# Nutriente_superior.net
KiCad netlist of a schematic drawn in EAGLE
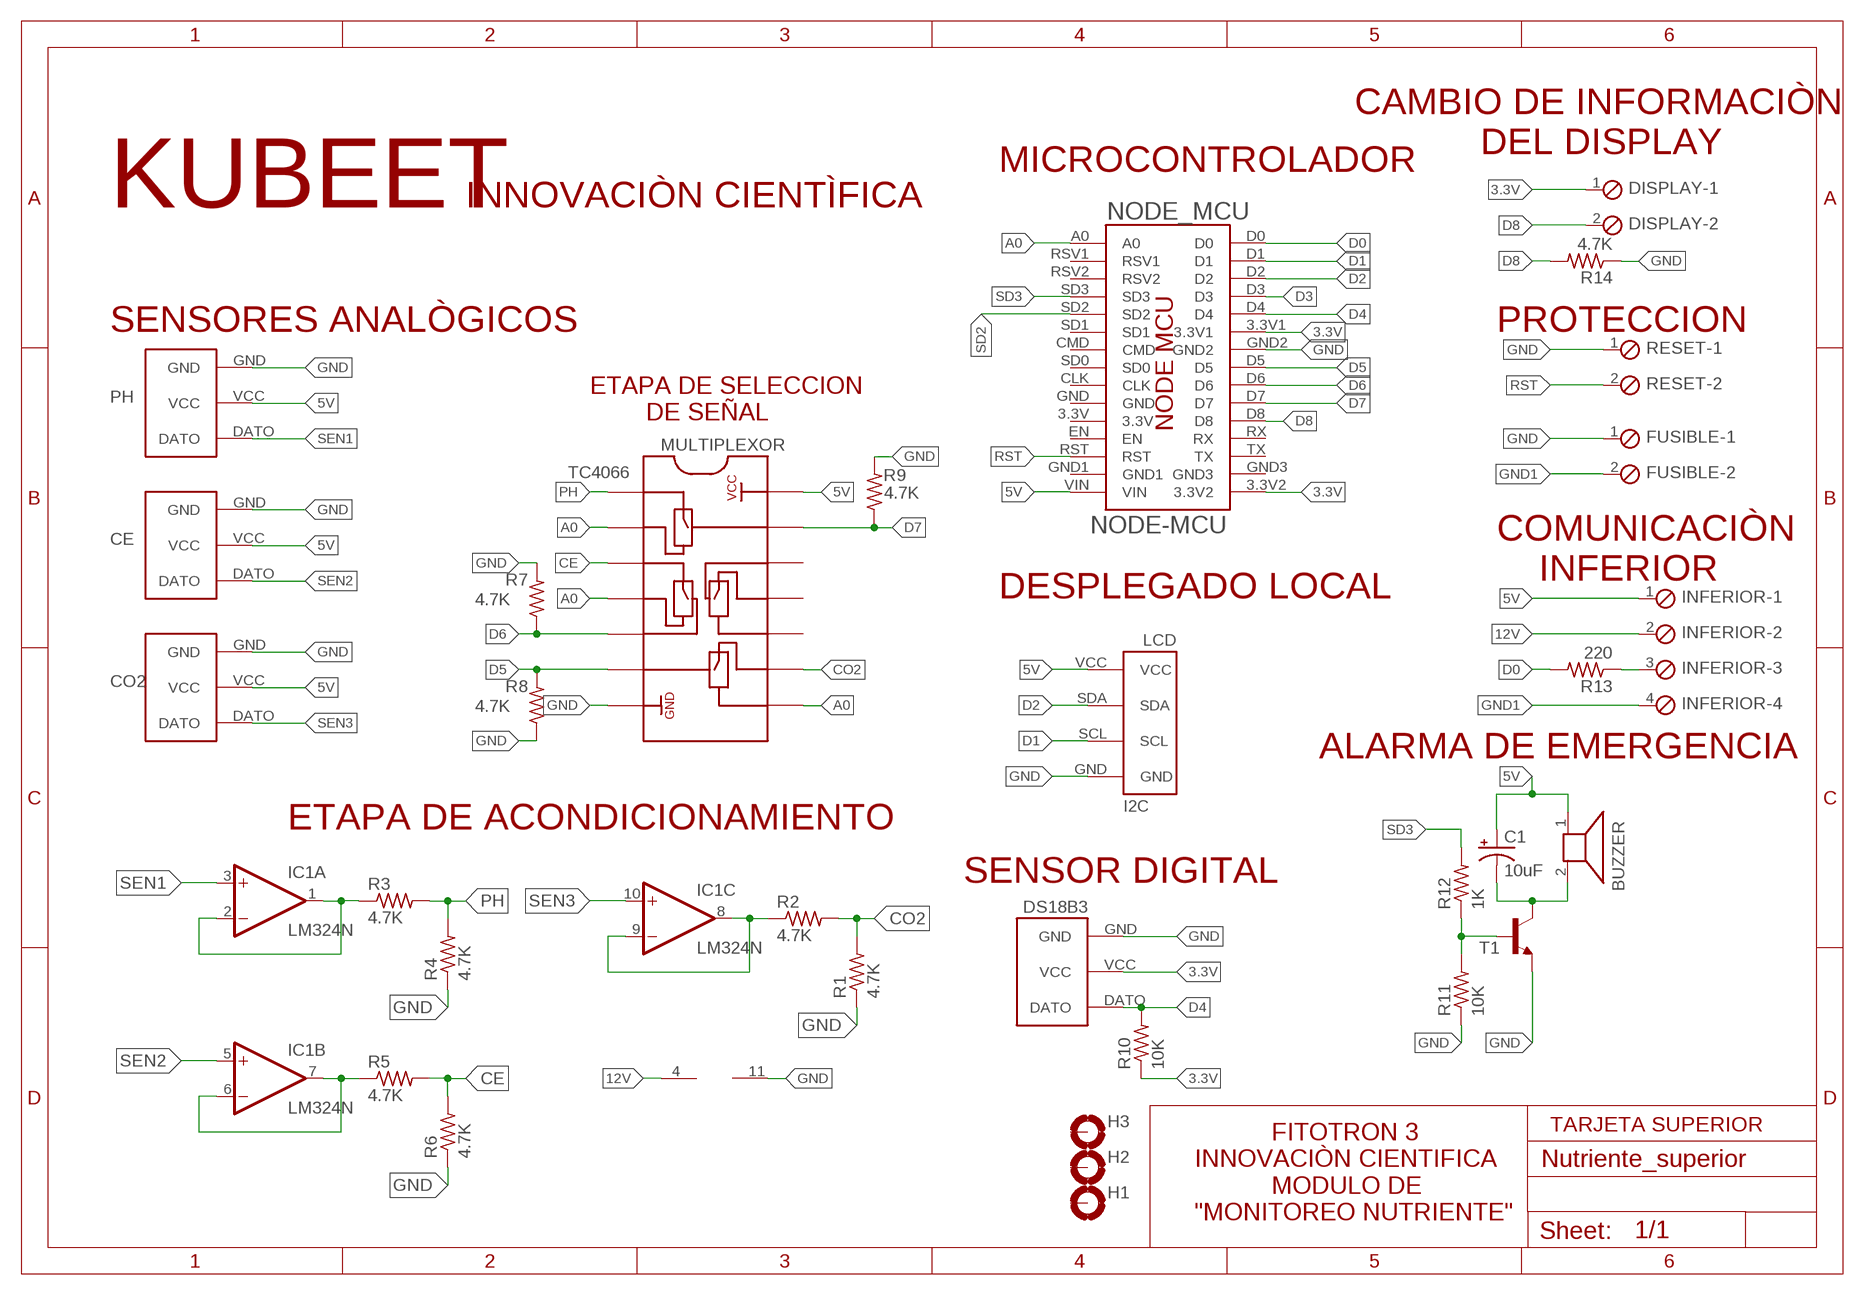
[diagram p0: schematic, sheet 1]

(export (version "E")
  (design (tool "Eeschema 10.0.6"))
  (components
    (comp (ref "BUZZER")
      (value "AL60P")
      (footprint "eagle-import:AL60P")
      (libsource (lib "eagle-import") (part "AL60P"))
    )
    (comp (ref "C1")
      (value "10uF")
      (footprint "eagle-import:E2,5-6")
      (libsource (lib "eagle-import") (part "CPOL-USE2.5-6"))
    )
    (comp (ref "CE")
      (value "BASE")
      (footprint "eagle-import:BASE")
      (libsource (lib "eagle-import") (part "BASE"))
    )
    (comp (ref "CO2")
      (value "BASE")
      (footprint "eagle-import:BASE")
      (libsource (lib "eagle-import") (part "BASE"))
    )
    (comp (ref "DISPLAY")
      (value "MPT2")
      (footprint "eagle-import:2POL254")
      (libsource (lib "eagle-import") (part "MPT2"))
    )
    (comp (ref "DS18B3")
      (value "BASE")
      (footprint "eagle-import:BASE")
      (libsource (lib "eagle-import") (part "BASE"))
    )
    (comp (ref "FUSIBLE")
      (value "MPT2")
      (footprint "eagle-import:2POL254")
      (libsource (lib "eagle-import") (part "MPT2"))
    )
    (comp (ref "H1")
      (value "MOUNT-PAD-ROUND3.0")
      (footprint "eagle-import:3,0-PAD")
      (libsource (lib "eagle-import") (part "MOUNT-PAD-ROUND3.0"))
    )
    (comp (ref "H2")
      (value "MOUNT-PAD-ROUND3.0")
      (footprint "eagle-import:3,0-PAD")
      (libsource (lib "eagle-import") (part "MOUNT-PAD-ROUND3.0"))
    )
    (comp (ref "H3")
      (value "MOUNT-PAD-ROUND3.0")
      (footprint "eagle-import:3,0-PAD")
      (libsource (lib "eagle-import") (part "MOUNT-PAD-ROUND3.0"))
    )
    (comp (ref "IC1")
      (value "LM324N")
      (footprint "eagle-import:DIL14")
      (libsource (lib "eagle-import") (part "LM324N"))
    )
    (comp (ref "INFERIOR")
      (value "MPT4")
      (footprint "eagle-import:4POL254")
      (libsource (lib "eagle-import") (part "MPT4"))
    )
    (comp (ref "LCD")
      (value "I2C")
      (footprint "eagle-import:I2C")
      (libsource (lib "eagle-import") (part "I2C"))
    )
    (comp (ref "MULTIPLEXOR")
      (value "TC4066")
      (footprint "eagle-import:TC4066")
      (libsource (lib "eagle-import") (part "TC4066"))
    )
    (comp (ref "NODE_MCU")
      (value "NODE-MCU")
      (footprint "eagle-import:NODE-MCU")
      (libsource (lib "eagle-import") (part "NODE-MCU"))
    )
    (comp (ref "PH")
      (value "BASE")
      (footprint "eagle-import:BASE")
      (libsource (lib "eagle-import") (part "BASE"))
    )
    (comp (ref "R1")
      (value "4.7K")
      (footprint "eagle-import:0207_7")
      (libsource (lib "eagle-import") (part "R-US_0207/7"))
    )
    (comp (ref "R2")
      (value "4.7K")
      (footprint "eagle-import:0207_7")
      (libsource (lib "eagle-import") (part "R-US_0207/7"))
    )
    (comp (ref "R3")
      (value "4.7K")
      (footprint "eagle-import:0207_7")
      (libsource (lib "eagle-import") (part "R-US_0207/7"))
    )
    (comp (ref "R4")
      (value "4.7K")
      (footprint "eagle-import:0207_7")
      (libsource (lib "eagle-import") (part "R-US_0207/7"))
    )
    (comp (ref "R5")
      (value "4.7K")
      (footprint "eagle-import:0207_7")
      (libsource (lib "eagle-import") (part "R-US_0207/7"))
    )
    (comp (ref "R6")
      (value "4.7K")
      (footprint "eagle-import:0207_7")
      (libsource (lib "eagle-import") (part "R-US_0207/7"))
    )
    (comp (ref "R7")
      (value "4.7K")
      (footprint "eagle-import:0207_7")
      (libsource (lib "eagle-import") (part "R-US_0207/7"))
    )
    (comp (ref "R8")
      (value "4.7K")
      (footprint "eagle-import:0207_7")
      (libsource (lib "eagle-import") (part "R-US_0207/7"))
    )
    (comp (ref "R9")
      (value "4.7K")
      (footprint "eagle-import:0207_7")
      (libsource (lib "eagle-import") (part "R-US_0207/7"))
    )
    (comp (ref "R10")
      (value "10K")
      (footprint "eagle-import:0207_7")
      (libsource (lib "eagle-import") (part "R-US_0207/7"))
    )
    (comp (ref "R11")
      (value "10K")
      (footprint "eagle-import:0207_7")
      (libsource (lib "eagle-import") (part "R-US_0207/7"))
    )
    (comp (ref "R12")
      (value "1K")
      (footprint "eagle-import:0207_7")
      (libsource (lib "eagle-import") (part "R-US_0207/7"))
    )
    (comp (ref "R13")
      (value "220")
      (footprint "eagle-import:0207_10")
      (libsource (lib "eagle-import") (part "R-US_0207/10"))
    )
    (comp (ref "R14")
      (value "4.7K")
      (footprint "eagle-import:0207_7")
      (libsource (lib "eagle-import") (part "R-US_0207/7"))
    )
    (comp (ref "RESET")
      (value "MPT2")
      (footprint "eagle-import:2POL254")
      (libsource (lib "eagle-import") (part "MPT2"))
    )
    (comp (ref "T1")
      (value "2N2222-NPN-TO92-EBC")
      (footprint "eagle-import:TO92-EBC")
      (libsource (lib "eagle-import") (part "-NPN-TO92-EBC2N2222"))
    )
  )
  (nets
    (net (code "1") (name "3.3V") (class "Default")
      (node (ref "DISPLAY") (pin "1") (pinfunction "1_1") (pintype "passive"))
      (node (ref "DS18B3") (pin "VCC") (pinfunction "VCC_VCC") (pintype "bidirectional"))
      (node (ref "NODE_MCU") (pin "3.3V1") (pinfunction "3.3V1_3.3V1") (pintype "bidirectional"))
      (node (ref "NODE_MCU") (pin "3.3V2") (pinfunction "3.3V2_3.3V2") (pintype "bidirectional"))
      (node (ref "R10") (pin "1") (pinfunction "1_1") (pintype "passive"))
    )
    (net (code "2") (name "5V") (class "Default")
      (node (ref "BUZZER") (pin "1") (pinfunction "1_1") (pintype "passive"))
      (node (ref "C1") (pin "+") (pinfunction "+_+") (pintype "passive"))
      (node (ref "CE") (pin "VCC") (pinfunction "VCC_VCC") (pintype "bidirectional"))
      (node (ref "CO2") (pin "VCC") (pinfunction "VCC_VCC") (pintype "bidirectional"))
      (node (ref "INFERIOR") (pin "1") (pinfunction "1_1") (pintype "passive"))
      (node (ref "LCD") (pin "VCC") (pinfunction "VCC_VCC") (pintype "bidirectional"))
      (node (ref "MULTIPLEXOR") (pin "14") (pinfunction "14_14") (pintype "bidirectional"))
      (node (ref "NODE_MCU") (pin "VIN") (pinfunction "VIN_VIN") (pintype "bidirectional"))
      (node (ref "PH") (pin "VCC") (pinfunction "VCC_VCC") (pintype "bidirectional"))
    )
    (net (code "3") (name "12V") (class "Default")
      (node (ref "IC1") (pin "4") (pinfunction "V+_4") (pintype "power_in"))
      (node (ref "INFERIOR") (pin "2") (pinfunction "1_2") (pintype "passive"))
    )
    (net (code "4") (name "A0") (class "Default")
      (node (ref "MULTIPLEXOR") (pin "2") (pinfunction "2_2") (pintype "bidirectional"))
      (node (ref "MULTIPLEXOR") (pin "4") (pinfunction "4_4") (pintype "bidirectional"))
      (node (ref "MULTIPLEXOR") (pin "8") (pinfunction "8_8") (pintype "bidirectional"))
      (node (ref "NODE_MCU") (pin "A0") (pinfunction "A0_A0") (pintype "bidirectional"))
    )
    (net (code "5") (name "CE") (class "Default")
      (node (ref "MULTIPLEXOR") (pin "3") (pinfunction "3_3") (pintype "bidirectional"))
      (node (ref "R5") (pin "2") (pinfunction "2_2") (pintype "passive"))
      (node (ref "R6") (pin "2") (pinfunction "2_2") (pintype "passive"))
    )
    (net (code "6") (name "CO2") (class "Default")
      (node (ref "MULTIPLEXOR") (pin "9") (pinfunction "9_9") (pintype "bidirectional"))
      (node (ref "R1") (pin "2") (pinfunction "2_2") (pintype "passive"))
      (node (ref "R2") (pin "2") (pinfunction "2_2") (pintype "passive"))
    )
    (net (code "7") (name "D0") (class "Default")
      (node (ref "NODE_MCU") (pin "D0") (pinfunction "D0_D0") (pintype "bidirectional"))
      (node (ref "R13") (pin "2") (pinfunction "2_2") (pintype "passive"))
    )
    (net (code "8") (name "D1") (class "Default")
      (node (ref "LCD") (pin "SCL") (pinfunction "SCL_SCL") (pintype "bidirectional"))
      (node (ref "NODE_MCU") (pin "D1") (pinfunction "D1_D1") (pintype "bidirectional"))
    )
    (net (code "9") (name "D2") (class "Default")
      (node (ref "LCD") (pin "SDA") (pinfunction "SDA_SDA") (pintype "bidirectional"))
      (node (ref "NODE_MCU") (pin "D2") (pinfunction "D2_D2") (pintype "bidirectional"))
    )
    (net (code "10") (name "D3") (class "Default")
      (node (ref "NODE_MCU") (pin "D3") (pinfunction "D3_D3") (pintype "bidirectional"))
    )
    (net (code "11") (name "D4") (class "Default")
      (node (ref "DS18B3") (pin "DATO") (pinfunction "DATO_DATO") (pintype "bidirectional"))
      (node (ref "NODE_MCU") (pin "D4") (pinfunction "D4_D4") (pintype "bidirectional"))
      (node (ref "R10") (pin "2") (pinfunction "2_2") (pintype "passive"))
    )
    (net (code "12") (name "D5") (class "Default")
      (node (ref "MULTIPLEXOR") (pin "6") (pinfunction "6_6") (pintype "bidirectional"))
      (node (ref "NODE_MCU") (pin "D5") (pinfunction "D5_D5") (pintype "bidirectional"))
      (node (ref "R8") (pin "2") (pinfunction "2_2") (pintype "passive"))
    )
    (net (code "13") (name "D6") (class "Default")
      (node (ref "MULTIPLEXOR") (pin "5") (pinfunction "5_5") (pintype "bidirectional"))
      (node (ref "NODE_MCU") (pin "D6") (pinfunction "D6_D6") (pintype "bidirectional"))
      (node (ref "R7") (pin "1") (pinfunction "1_1") (pintype "passive"))
    )
    (net (code "14") (name "D7") (class "Default")
      (node (ref "MULTIPLEXOR") (pin "13") (pinfunction "13_13") (pintype "bidirectional"))
      (node (ref "NODE_MCU") (pin "D7") (pinfunction "D7_D7") (pintype "bidirectional"))
      (node (ref "R9") (pin "1") (pinfunction "1_1") (pintype "passive"))
    )
    (net (code "15") (name "D8") (class "Default")
      (node (ref "DISPLAY") (pin "2") (pinfunction "1_2") (pintype "passive"))
      (node (ref "NODE_MCU") (pin "D8") (pinfunction "D8_D8") (pintype "bidirectional"))
      (node (ref "R14") (pin "2") (pinfunction "2_2") (pintype "passive"))
    )
    (net (code "16") (name "GND") (class "Default")
      (node (ref "CE") (pin "GND") (pinfunction "GND_GND") (pintype "bidirectional"))
      (node (ref "CO2") (pin "GND") (pinfunction "GND_GND") (pintype "bidirectional"))
      (node (ref "DS18B3") (pin "GND") (pinfunction "GND_GND") (pintype "bidirectional"))
      (node (ref "FUSIBLE") (pin "1") (pinfunction "1_1") (pintype "passive"))
      (node (ref "IC1") (pin "11") (pinfunction "V-_11") (pintype "power_in"))
      (node (ref "LCD") (pin "GND") (pinfunction "GND_GND") (pintype "bidirectional"))
      (node (ref "MULTIPLEXOR") (pin "7") (pinfunction "7_7") (pintype "bidirectional"))
      (node (ref "NODE_MCU") (pin "GND2") (pinfunction "GND2_GND2") (pintype "bidirectional"))
      (node (ref "PH") (pin "GND") (pinfunction "GND_GND") (pintype "bidirectional"))
      (node (ref "R1") (pin "1") (pinfunction "1_1") (pintype "passive"))
      (node (ref "R11") (pin "1") (pinfunction "1_1") (pintype "passive"))
      (node (ref "R14") (pin "1") (pinfunction "1_1") (pintype "passive"))
      (node (ref "R4") (pin "1") (pinfunction "1_1") (pintype "passive"))
      (node (ref "R6") (pin "1") (pinfunction "1_1") (pintype "passive"))
      (node (ref "R7") (pin "2") (pinfunction "2_2") (pintype "passive"))
      (node (ref "R8") (pin "1") (pinfunction "1_1") (pintype "passive"))
      (node (ref "R9") (pin "2") (pinfunction "2_2") (pintype "passive"))
      (node (ref "RESET") (pin "1") (pinfunction "1_1") (pintype "passive"))
      (node (ref "T1") (pin "E") (pinfunction "E_E") (pintype "passive"))
    )
    (net (code "17") (name "GND1") (class "Default")
      (node (ref "FUSIBLE") (pin "2") (pinfunction "1_2") (pintype "passive"))
      (node (ref "INFERIOR") (pin "4") (pinfunction "1_4") (pintype "passive"))
    )
    (net (code "18") (name "Net-(BUZZER-Pad2)") (class "Default")
      (node (ref "BUZZER") (pin "2") (pinfunction "2_2") (pintype "passive"))
      (node (ref "C1") (pin "-") (pinfunction "-_-") (pintype "passive"))
      (node (ref "T1") (pin "C") (pinfunction "C_C") (pintype "passive"))
    )
    (net (code "19") (name "Net-(IC1A--IN)") (class "Default")
      (node (ref "IC1") (pin "1") (pinfunction "OUT_1") (pintype "output"))
      (node (ref "IC1") (pin "2") (pinfunction "-IN_2") (pintype "input"))
      (node (ref "R3") (pin "1") (pinfunction "1_1") (pintype "passive"))
    )
    (net (code "20") (name "Net-(IC1B--IN)") (class "Default")
      (node (ref "IC1") (pin "6") (pinfunction "-IN_6") (pintype "input"))
      (node (ref "IC1") (pin "7") (pinfunction "OUT_7") (pintype "output"))
      (node (ref "R5") (pin "1") (pinfunction "1_1") (pintype "passive"))
    )
    (net (code "21") (name "Net-(IC1C--IN)") (class "Default")
      (node (ref "IC1") (pin "8") (pinfunction "OUT_8") (pintype "output"))
      (node (ref "IC1") (pin "9") (pinfunction "-IN_9") (pintype "input"))
      (node (ref "R2") (pin "1") (pinfunction "1_1") (pintype "passive"))
    )
    (net (code "22") (name "Net-(INFERIORC-1)") (class "Default")
      (node (ref "INFERIOR") (pin "3") (pinfunction "1_3") (pintype "passive"))
      (node (ref "R13") (pin "1") (pinfunction "1_1") (pintype "passive"))
    )
    (net (code "23") (name "Net-(R11-Pad2)") (class "Default")
      (node (ref "R11") (pin "2") (pinfunction "2_2") (pintype "passive"))
      (node (ref "R12") (pin "1") (pinfunction "1_1") (pintype "passive"))
      (node (ref "T1") (pin "B") (pinfunction "B_B") (pintype "passive"))
    )
    (net (code "24") (name "PH") (class "Default")
      (node (ref "MULTIPLEXOR") (pin "1") (pinfunction "1_1") (pintype "bidirectional"))
      (node (ref "R3") (pin "2") (pinfunction "2_2") (pintype "passive"))
      (node (ref "R4") (pin "2") (pinfunction "2_2") (pintype "passive"))
    )
    (net (code "25") (name "RST") (class "Default")
      (node (ref "NODE_MCU") (pin "RST") (pinfunction "RST_RST") (pintype "bidirectional"))
      (node (ref "RESET") (pin "2") (pinfunction "1_2") (pintype "passive"))
    )
    (net (code "26") (name "SD2") (class "Default")
      (node (ref "NODE_MCU") (pin "SD2") (pinfunction "SD2_SD2") (pintype "bidirectional"))
    )
    (net (code "27") (name "SD3") (class "Default")
      (node (ref "NODE_MCU") (pin "SD3") (pinfunction "SD3_SD3") (pintype "bidirectional"))
      (node (ref "R12") (pin "2") (pinfunction "2_2") (pintype "passive"))
    )
    (net (code "28") (name "SEN1") (class "Default")
      (node (ref "IC1") (pin "3") (pinfunction "+IN_3") (pintype "input"))
      (node (ref "PH") (pin "DATO") (pinfunction "DATO_DATO") (pintype "bidirectional"))
    )
    (net (code "29") (name "SEN2") (class "Default")
      (node (ref "CE") (pin "DATO") (pinfunction "DATO_DATO") (pintype "bidirectional"))
      (node (ref "IC1") (pin "5") (pinfunction "+IN_5") (pintype "input"))
    )
    (net (code "30") (name "SEN3") (class "Default")
      (node (ref "CO2") (pin "DATO") (pinfunction "DATO_DATO") (pintype "bidirectional"))
      (node (ref "IC1") (pin "10") (pinfunction "+IN_10") (pintype "input"))
    )
    (net (code "31") (name "unconnected-(H1-MOUNT-PadB3,0)") (class "Default")
      (node (ref "H1") (pin "B3,0") (pinfunction "MOUNT_B3,0") (pintype "passive"))
    )
    (net (code "32") (name "unconnected-(H2-MOUNT-PadB3,0)") (class "Default")
      (node (ref "H2") (pin "B3,0") (pinfunction "MOUNT_B3,0") (pintype "passive"))
    )
    (net (code "33") (name "unconnected-(H3-MOUNT-PadB3,0)") (class "Default")
      (node (ref "H3") (pin "B3,0") (pinfunction "MOUNT_B3,0") (pintype "passive"))
    )
    (net (code "34") (name "unconnected-(MULTIPLEXOR-Pad10)") (class "Default")
      (node (ref "MULTIPLEXOR") (pin "10") (pinfunction "10_10") (pintype "bidirectional"))
    )
    (net (code "35") (name "unconnected-(MULTIPLEXOR-Pad11)") (class "Default")
      (node (ref "MULTIPLEXOR") (pin "11") (pinfunction "11_11") (pintype "bidirectional"))
    )
    (net (code "36") (name "unconnected-(MULTIPLEXOR-Pad12)") (class "Default")
      (node (ref "MULTIPLEXOR") (pin "12") (pinfunction "12_12") (pintype "bidirectional"))
    )
    (net (code "37") (name "unconnected-(NODE_MCU-Pad3.3V)") (class "Default")
      (node (ref "NODE_MCU") (pin "3.3V") (pinfunction "3.3V_3.3V") (pintype "bidirectional"))
    )
    (net (code "38") (name "unconnected-(NODE_MCU-PadCLK)") (class "Default")
      (node (ref "NODE_MCU") (pin "CLK") (pinfunction "CLK_CLK") (pintype "bidirectional"))
    )
    (net (code "39") (name "unconnected-(NODE_MCU-PadCMD)") (class "Default")
      (node (ref "NODE_MCU") (pin "CMD") (pinfunction "CMD_CMD") (pintype "bidirectional"))
    )
    (net (code "40") (name "unconnected-(NODE_MCU-PadEN)") (class "Default")
      (node (ref "NODE_MCU") (pin "EN") (pinfunction "EN_EN") (pintype "bidirectional"))
    )
    (net (code "41") (name "unconnected-(NODE_MCU-PadGND)") (class "Default")
      (node (ref "NODE_MCU") (pin "GND") (pinfunction "GND_GND") (pintype "bidirectional"))
    )
    (net (code "42") (name "unconnected-(NODE_MCU-PadGND1)") (class "Default")
      (node (ref "NODE_MCU") (pin "GND1") (pinfunction "GND1_GND1") (pintype "bidirectional"))
    )
    (net (code "43") (name "unconnected-(NODE_MCU-PadGND3)") (class "Default")
      (node (ref "NODE_MCU") (pin "GND3") (pinfunction "GND3_GND3") (pintype "bidirectional"))
    )
    (net (code "44") (name "unconnected-(NODE_MCU-PadRSV1)") (class "Default")
      (node (ref "NODE_MCU") (pin "RSV1") (pinfunction "RSV1_RSV1") (pintype "bidirectional"))
    )
    (net (code "45") (name "unconnected-(NODE_MCU-PadRSV2)") (class "Default")
      (node (ref "NODE_MCU") (pin "RSV2") (pinfunction "RSV2_RSV2") (pintype "bidirectional"))
    )
    (net (code "46") (name "unconnected-(NODE_MCU-PadRX)") (class "Default")
      (node (ref "NODE_MCU") (pin "RX") (pinfunction "RX_RX") (pintype "bidirectional"))
    )
    (net (code "47") (name "unconnected-(NODE_MCU-PadSD0)") (class "Default")
      (node (ref "NODE_MCU") (pin "SD0") (pinfunction "SD0_SD0") (pintype "bidirectional"))
    )
    (net (code "48") (name "unconnected-(NODE_MCU-PadSD1)") (class "Default")
      (node (ref "NODE_MCU") (pin "SD1") (pinfunction "SD1_SD1") (pintype "bidirectional"))
    )
    (net (code "49") (name "unconnected-(NODE_MCU-PadTX)") (class "Default")
      (node (ref "NODE_MCU") (pin "TX") (pinfunction "TX_TX") (pintype "bidirectional"))
    )
  )
)
